# ChassisSupply_v1_0_2.net
KiCad netlist of a schematic drawn in EasyEDA Pro
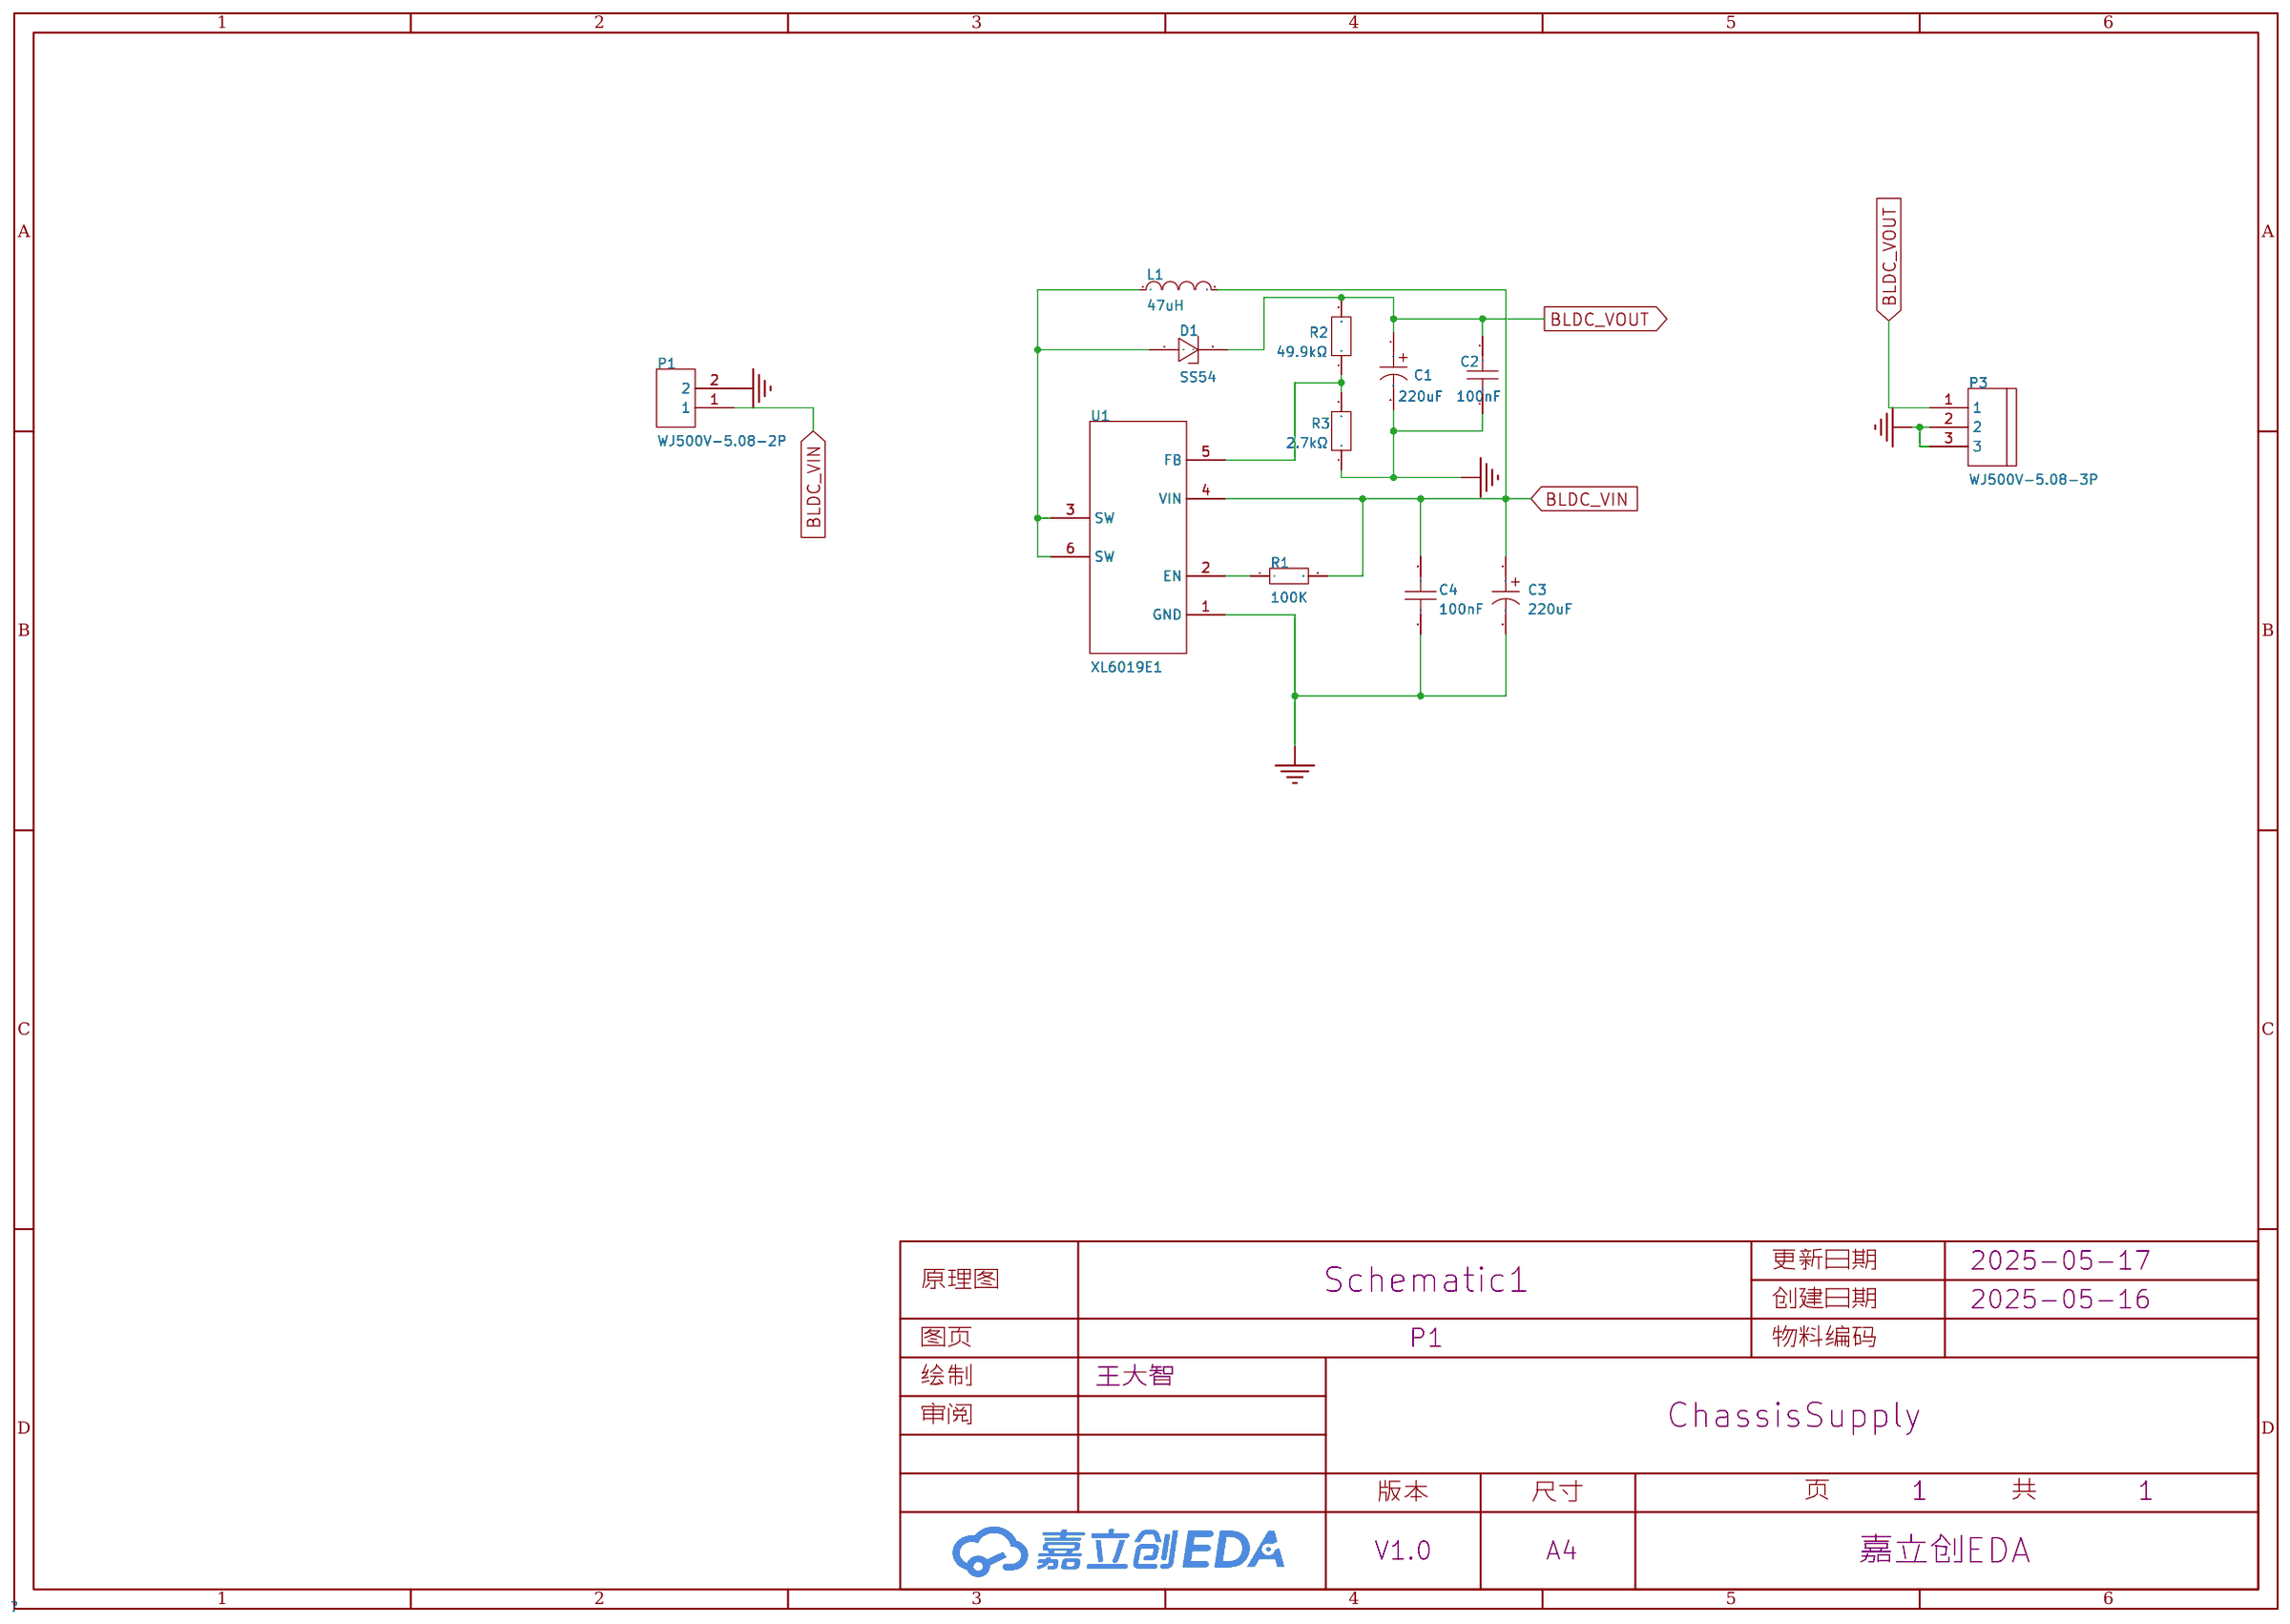
[diagram p0: schematic sheet]

(export (version "E")
  (design (tool "Eeschema 10.0.6"))
  (components
    (comp (ref "C1")
      (value "220uF")
      (footprint "easyedapro:CAP-SMD_BD8.0-L8.3-W8.3-FD")
      (description "容值:220uF;精度:±20%;额定电压:35V;纹波电流:175mA@120Hz;")
      (fields
        (field (name "Manufacturer Part") "GVT1V227M0810CNVC")
        (field (name "Manufacturer") "HRK(鸿瑞凯电子)")
      )
      (libsource (lib "easyedapro") (part "GVT1V227M0810CNVC"))
    )
    (comp (ref "C2")
      (value "100nF")
      (footprint "easyedapro:C0603")
      (libsource (lib "easyedapro") (part "CapAcitance"))
    )
    (comp (ref "C3")
      (value "220uF")
      (footprint "easyedapro:CAP-SMD_BD8.0-L8.3-W8.3-FD")
      (description "容值:220uF;精度:±20%;额定电压:35V;纹波电流:175mA@120Hz;")
      (fields
        (field (name "Manufacturer Part") "GVT1V227M0810CNVC")
        (field (name "Manufacturer") "HRK(鸿瑞凯电子)")
      )
      (libsource (lib "easyedapro") (part "GVT1V227M0810CNVC"))
    )
    (comp (ref "C4")
      (value "100nF")
      (footprint "easyedapro:C0603")
      (libsource (lib "easyedapro") (part "CapAcitance"))
    )
    (comp (ref "D1")
      (value "SS54")
      (footprint "easyedapro:SMA_L4.3-W2.6-LS5.0-FD")
      (description "二极管配置:独立式;正向压降(Vf):550mV@5.0A;直流反向耐压(Vr):40V;整流电流:5A;")
      (fields (field (name "Manufacturer") "宏迦橙"))
      (libsource (lib "easyedapro") (part "SS54_C7420369"))
    )
    (comp (ref "L1")
      (value "47uH")
      (footprint "easyedapro:IND-SMD_L11.5-W10.0_SMMS1040")
      (description "电感值:47uH;精度:±20%;额定电流:3A;饱和电流(Isat):4.5A;类型:一体成型电感;")
      (fields (field (name "Manufacturer Part") "SMMS1040-470M") (field (name "Manufacturer") "SXN(顺翔诺)"))
      (libsource (lib "easyedapro") (part "SMMS1040-470M"))
    )
    (comp (ref "P1")
      (value "WJ500V-5.08-2P")
      (footprint "easyedapro:CONN-TH_2P-P5.00_WJ500V-5.08-2P")
      (fields (field (name "Manufacturer") "KANGNEX(康奈克斯电气)"))
      (libsource (lib "easyedapro") (part "WJ500V-5.08-2P-14-00A"))
    )
    (comp (ref "P3")
      (value "WJ500V-5.08-3P")
      (footprint "easyedapro:CONN-TH_3P-P5.00_WJ500V-5.08-3P")
      (fields (field (name "Manufacturer") "KANGNEX(康奈克斯电气)"))
      (libsource (lib "easyedapro") (part "WJ500V-5.08-3P-14-00A"))
    )
    (comp (ref "R1") (value "100K") (footprint "easyedapro:R0603") (libsource (lib "easyedapro") (part "电阻")))
    (comp (ref "R2")
      (value "49.9kΩ")
      (footprint "easyedapro:R0603")
      (description "电阻类型:厚膜电阻;阻值:49.9kΩ;精度:±1%;功率:100mW;最大工作电压:75V;温度系数:±100ppm/°C;")
      (fields (field (name "Manufacturer Part") "FRC0603F4992TS") (field (name "Manufacturer") "FOJAN(富捷)"))
      (libsource (lib "easyedapro") (part "FRC0603F4992TS"))
    )
    (comp (ref "R3")
      (value "2.7kΩ")
      (footprint "easyedapro:R0603")
      (description "电阻类型:厚膜电阻;阻值:2.7kΩ;精度:±1%;功率:100mW;工作电压:75V;温度系数:±100ppm/°C;")
      (fields (field (name "Manufacturer Part") "FRC0603F2701TS") (field (name "Manufacturer") "FOJAN(富捷)"))
      (libsource (lib "easyedapro") (part "FRC0603F2701TS"))
    )
    (comp (ref "U1")
      (value "XL6019E1")
      (footprint "easyedapro:TO-263-5_L10.2-W9.9-P1.70-LS14.4-TL")
      (description "功能类型:升降压型;输出类型:可调;工作电压:5V~40V;输出电压:-;输出电流:5A;")
      (fields (field (name "Manufacturer") "XLSEMI(芯龙)"))
      (libsource (lib "easyedapro") (part "XL6019E1"))
    )
  )
  (nets
    (net (code "1") (name "BLDC_VIN") (class "Default")
      (node (ref "C3") (pin "1") (pinfunction "1_1") (pintype "input"))
      (node (ref "C4") (pin "1") (pinfunction "1_1") (pintype "input"))
      (node (ref "L1") (pin "2") (pinfunction "2_2") (pintype "unspecified"))
      (node (ref "P1") (pin "1") (pinfunction "1_1") (pintype "unspecified"))
      (node (ref "R1") (pin "2") (pinfunction "2_2") (pintype "input"))
      (node (ref "U1") (pin "4") (pinfunction "VIN_4") (pintype "unspecified"))
    )
    (net (code "2") (name "BLDC_VOUT") (class "Default")
      (node (ref "C1") (pin "1") (pinfunction "1_1") (pintype "input"))
      (node (ref "C2") (pin "2") (pinfunction "2_2") (pintype "input"))
      (node (ref "D1") (pin "2") (pinfunction "K_2") (pintype "unspecified"))
      (node (ref "P3") (pin "1") (pinfunction "1_1") (pintype "unspecified"))
      (node (ref "R2") (pin "2") (pinfunction "2_2") (pintype "unspecified"))
    )
    (net (code "3") (name "GND") (class "Default")
      (node (ref "C1") (pin "2") (pinfunction "2_2") (pintype "input"))
      (node (ref "C2") (pin "1") (pinfunction "1_1") (pintype "input"))
      (node (ref "C3") (pin "2") (pinfunction "2_2") (pintype "input"))
      (node (ref "C4") (pin "2") (pinfunction "2_2") (pintype "input"))
      (node (ref "P1") (pin "2") (pinfunction "2_2") (pintype "unspecified"))
      (node (ref "P3") (pin "2") (pinfunction "2_2") (pintype "unspecified"))
      (node (ref "P3") (pin "3") (pinfunction "3_3") (pintype "unspecified"))
      (node (ref "R3") (pin "1") (pinfunction "1_1") (pintype "unspecified"))
      (node (ref "U1") (pin "1") (pinfunction "GND_1") (pintype "unspecified"))
    )
    (net (code "4") (name "Net-(D1-A)") (class "Default")
      (node (ref "D1") (pin "1") (pinfunction "A_1") (pintype "unspecified"))
      (node (ref "L1") (pin "1") (pinfunction "1_1") (pintype "unspecified"))
      (node (ref "U1") (pin "3") (pinfunction "SW_3") (pintype "unspecified"))
      (node (ref "U1") (pin "6") (pinfunction "SW_6") (pintype "unspecified"))
    )
    (net (code "5") (name "Net-(U1-EN)") (class "Default")
      (node (ref "R1") (pin "1") (pinfunction "1_1") (pintype "input"))
      (node (ref "U1") (pin "2") (pinfunction "EN_2") (pintype "unspecified"))
    )
    (net (code "6") (name "Net-(U1-FB)") (class "Default")
      (node (ref "R2") (pin "1") (pinfunction "1_1") (pintype "unspecified"))
      (node (ref "R3") (pin "2") (pinfunction "2_2") (pintype "unspecified"))
      (node (ref "U1") (pin "5") (pinfunction "FB_5") (pintype "unspecified"))
    )
  )
)
